# 1A20J1_1A21J2_B.net
KiCad netlist of a schematic drawn in Altium Designer
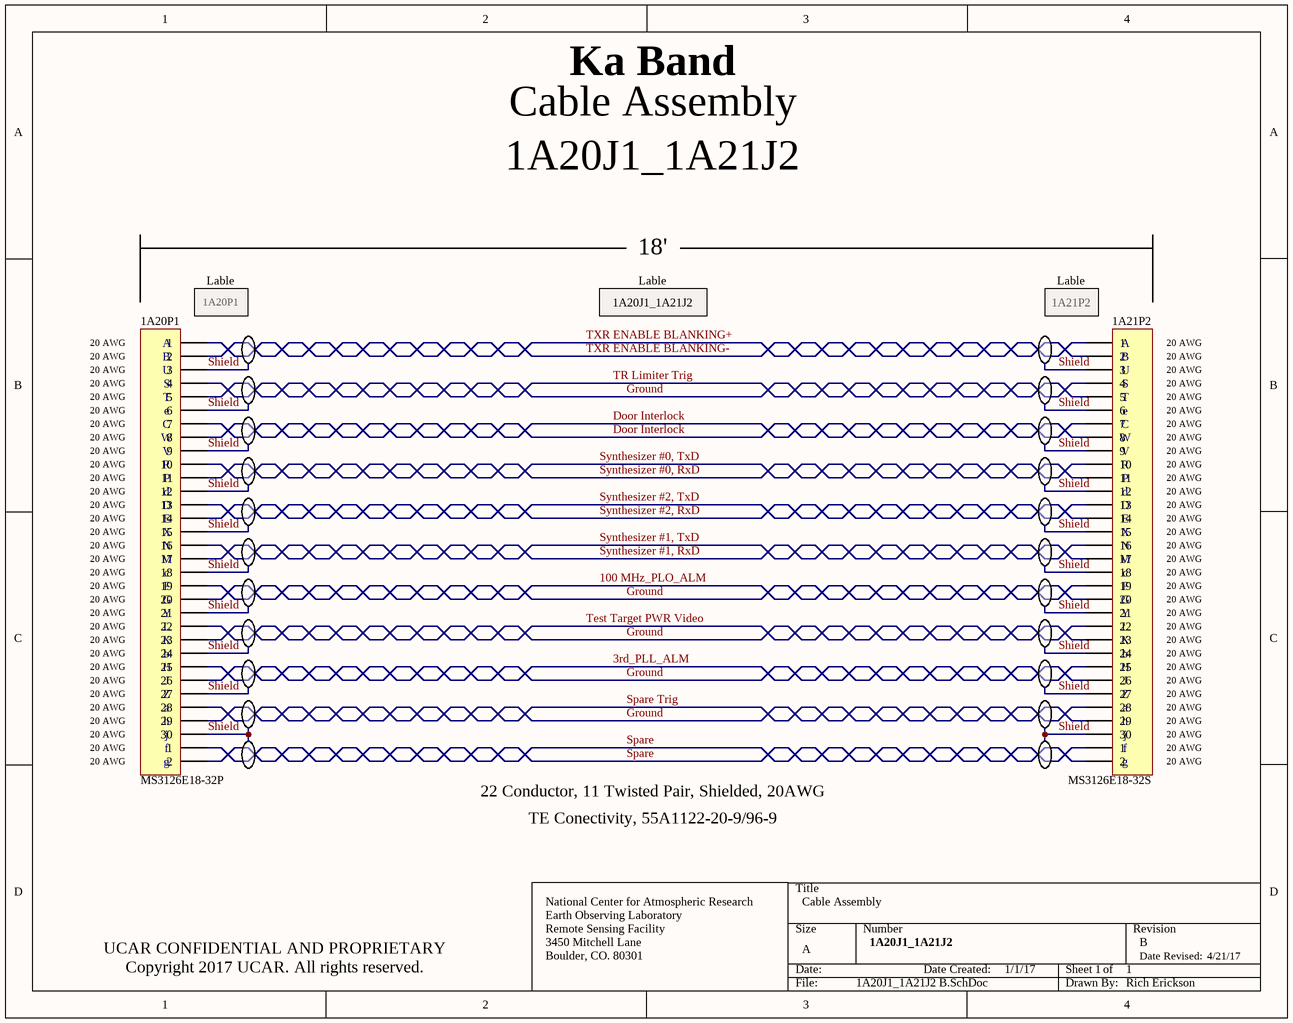
[diagram p0: 1A20J1_1A21J2 B.SchDoc]

(export (version "E")
  (design (tool "Eeschema 10.0.6"))
  (components
    (comp (ref "1A20P1")
      (value "MS3126E18-32P")
      (footprint "HDR1X30")
      (description "Header, 30-Pin")
      (fields (field (name "PUBLISHER") "Altium Limited"))
      (libsource (lib "Miscellaneous Connectors") (part "Header 30"))
    )
    (comp (ref "1A20P1a")
      (value "MS3126E18-32P")
      (footprint "HDR1X2")
      (description "Header, 2-Pin")
      (fields (field (name "PUBLISHER") "Altium Limited"))
      (libsource (lib "Miscellaneous Connectors") (part "Header 2"))
    )
    (comp (ref "1A21P2")
      (value "MS3126E18-32S")
      (footprint "HDR1X30")
      (description "Header, 30-Pin")
      (fields (field (name "PUBLISHER") "Altium Limited"))
      (libsource (lib "") (part "Header 30_1"))
    )
    (comp (ref "1A21P2a")
      (value "MS3126E18-32S")
      (footprint "HDR1X2")
      (description "Header, 2-Pin")
      (fields (field (name "PUBLISHER") "Altium Limited"))
      (libsource (lib "") (part "Header 2_1"))
    )
  )
  (nets
    (net (code "1") (name "/3rd_PLL_ALM") (class "Default")
      (node (ref "1A20P1") (pin "25") (pinfunction "25_25") (pintype "passive"))
      (node (ref "1A21P2") (pin "25") (pinfunction "25_25") (pintype "passive"))
    )
    (net (code "2") (name "/100 MHz_PLO_ALM") (class "Default")
      (node (ref "1A20P1") (pin "19") (pinfunction "19_19") (pintype "passive"))
      (node (ref "1A21P2") (pin "19") (pinfunction "19_19") (pintype "passive"))
    )
    (net (code "3") (name "/Door Interlock") (class "Default")
      (node (ref "1A20P1") (pin "7") (pinfunction "7_7") (pintype "passive"))
      (node (ref "1A20P1") (pin "8") (pinfunction "8_8") (pintype "passive"))
      (node (ref "1A21P2") (pin "7") (pinfunction "7_7") (pintype "passive"))
      (node (ref "1A21P2") (pin "8") (pinfunction "8_8") (pintype "passive"))
    )
    (net (code "4") (name "/Ground") (class "Default")
      (node (ref "1A20P1") (pin "20") (pinfunction "20_20") (pintype "passive"))
      (node (ref "1A20P1") (pin "23") (pinfunction "23_23") (pintype "passive"))
      (node (ref "1A20P1") (pin "26") (pinfunction "26_26") (pintype "passive"))
      (node (ref "1A20P1") (pin "29") (pinfunction "29_29") (pintype "passive"))
      (node (ref "1A20P1") (pin "5") (pinfunction "5_5") (pintype "passive"))
      (node (ref "1A21P2") (pin "20") (pinfunction "20_20") (pintype "passive"))
      (node (ref "1A21P2") (pin "23") (pinfunction "23_23") (pintype "passive"))
      (node (ref "1A21P2") (pin "26") (pinfunction "26_26") (pintype "passive"))
      (node (ref "1A21P2") (pin "29") (pinfunction "29_29") (pintype "passive"))
      (node (ref "1A21P2") (pin "5") (pinfunction "5_5") (pintype "passive"))
    )
    (net (code "5") (name "/Shield") (class "Default")
      (node (ref "1A20P1") (pin "12") (pinfunction "12_12") (pintype "passive"))
      (node (ref "1A20P1") (pin "15") (pinfunction "15_15") (pintype "passive"))
      (node (ref "1A20P1") (pin "18") (pinfunction "18_18") (pintype "passive"))
      (node (ref "1A20P1") (pin "21") (pinfunction "21_21") (pintype "passive"))
      (node (ref "1A20P1") (pin "24") (pinfunction "24_24") (pintype "passive"))
      (node (ref "1A20P1") (pin "27") (pinfunction "27_27") (pintype "passive"))
      (node (ref "1A20P1") (pin "3") (pinfunction "3_3") (pintype "passive"))
      (node (ref "1A20P1") (pin "30") (pinfunction "30_30") (pintype "passive"))
      (node (ref "1A20P1") (pin "6") (pinfunction "6_6") (pintype "passive"))
      (node (ref "1A20P1") (pin "9") (pinfunction "9_9") (pintype "passive"))
      (node (ref "1A21P2") (pin "12") (pinfunction "12_12") (pintype "passive"))
      (node (ref "1A21P2") (pin "15") (pinfunction "15_15") (pintype "passive"))
      (node (ref "1A21P2") (pin "18") (pinfunction "18_18") (pintype "passive"))
      (node (ref "1A21P2") (pin "21") (pinfunction "21_21") (pintype "passive"))
      (node (ref "1A21P2") (pin "24") (pinfunction "24_24") (pintype "passive"))
      (node (ref "1A21P2") (pin "27") (pinfunction "27_27") (pintype "passive"))
      (node (ref "1A21P2") (pin "3") (pinfunction "3_3") (pintype "passive"))
      (node (ref "1A21P2") (pin "30") (pinfunction "30_30") (pintype "passive"))
      (node (ref "1A21P2") (pin "6") (pinfunction "6_6") (pintype "passive"))
      (node (ref "1A21P2") (pin "9") (pinfunction "9_9") (pintype "passive"))
    )
    (net (code "6") (name "/Spare") (class "Default")
      (node (ref "1A20P1a") (pin "1") (pinfunction "1_1") (pintype "passive"))
      (node (ref "1A20P1a") (pin "2") (pinfunction "2_2") (pintype "passive"))
      (node (ref "1A21P2a") (pin "1") (pinfunction "1_1") (pintype "passive"))
      (node (ref "1A21P2a") (pin "2") (pinfunction "2_2") (pintype "passive"))
    )
    (net (code "7") (name "/Spare Trig") (class "Default")
      (node (ref "1A20P1") (pin "28") (pinfunction "28_28") (pintype "passive"))
      (node (ref "1A21P2") (pin "28") (pinfunction "28_28") (pintype "passive"))
    )
    (net (code "8") (name "/Synthesizer #0, RxD") (class "Default")
      (node (ref "1A20P1") (pin "11") (pinfunction "11_11") (pintype "passive"))
      (node (ref "1A21P2") (pin "11") (pinfunction "11_11") (pintype "passive"))
    )
    (net (code "9") (name "/Synthesizer #0, TxD") (class "Default")
      (node (ref "1A20P1") (pin "10") (pinfunction "10_10") (pintype "passive"))
      (node (ref "1A21P2") (pin "10") (pinfunction "10_10") (pintype "passive"))
    )
    (net (code "10") (name "/Synthesizer #1, RxD") (class "Default")
      (node (ref "1A20P1") (pin "17") (pinfunction "17_17") (pintype "passive"))
      (node (ref "1A21P2") (pin "17") (pinfunction "17_17") (pintype "passive"))
    )
    (net (code "11") (name "/Synthesizer #1, TxD") (class "Default")
      (node (ref "1A20P1") (pin "16") (pinfunction "16_16") (pintype "passive"))
      (node (ref "1A21P2") (pin "16") (pinfunction "16_16") (pintype "passive"))
    )
    (net (code "12") (name "/Synthesizer #2, RxD") (class "Default")
      (node (ref "1A20P1") (pin "14") (pinfunction "14_14") (pintype "passive"))
      (node (ref "1A21P2") (pin "14") (pinfunction "14_14") (pintype "passive"))
    )
    (net (code "13") (name "/Synthesizer #2, TxD") (class "Default")
      (node (ref "1A20P1") (pin "13") (pinfunction "13_13") (pintype "passive"))
      (node (ref "1A21P2") (pin "13") (pinfunction "13_13") (pintype "passive"))
    )
    (net (code "14") (name "/TR Limiter Trig") (class "Default")
      (node (ref "1A20P1") (pin "4") (pinfunction "4_4") (pintype "passive"))
      (node (ref "1A21P2") (pin "4") (pinfunction "4_4") (pintype "passive"))
    )
    (net (code "15") (name "/TXR ENABLE BLANKING+") (class "Default")
      (node (ref "1A20P1") (pin "1") (pinfunction "1_1") (pintype "passive"))
      (node (ref "1A21P2") (pin "1") (pinfunction "1_1") (pintype "passive"))
    )
    (net (code "16") (name "/TXR ENABLE BLANKING-") (class "Default")
      (node (ref "1A20P1") (pin "2") (pinfunction "2_2") (pintype "passive"))
      (node (ref "1A21P2") (pin "2") (pinfunction "2_2") (pintype "passive"))
    )
    (net (code "17") (name "/Test Target PWR Video") (class "Default")
      (node (ref "1A20P1") (pin "22") (pinfunction "22_22") (pintype "passive"))
      (node (ref "1A21P2") (pin "22") (pinfunction "22_22") (pintype "passive"))
    )
  )
)
